# interface_circuit.net
KiCad netlist of a schematic drawn in EAGLE
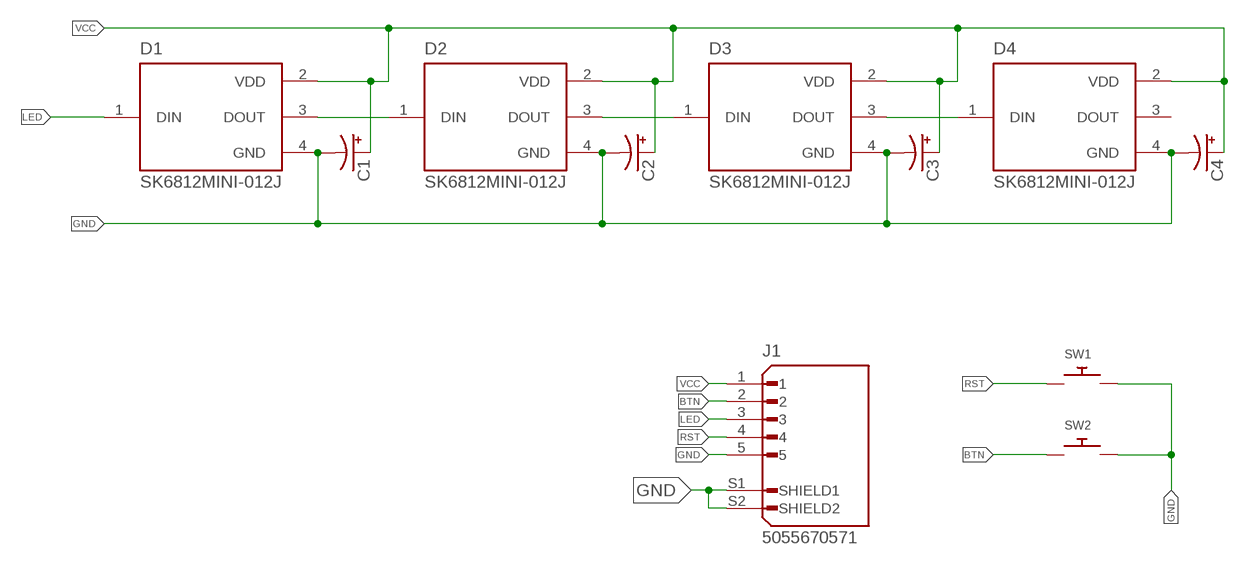
[diagram p0: schematic, sheet 1]

(export (version "E")
  (design (tool "Eeschema 10.0.6"))
  (components
    (comp (ref "C1")
      (value "CAP_POL1206")
      (footprint "eagle-import:EIA3216")
      (libsource (lib "eagle-import") (part "CAP_POL1206"))
    )
    (comp (ref "C2")
      (value "CAP_POL1206")
      (footprint "eagle-import:EIA3216")
      (libsource (lib "eagle-import") (part "CAP_POL1206"))
    )
    (comp (ref "C3")
      (value "CAP_POL1206")
      (footprint "eagle-import:EIA3216")
      (libsource (lib "eagle-import") (part "CAP_POL1206"))
    )
    (comp (ref "C4")
      (value "CAP_POL1206")
      (footprint "eagle-import:EIA3216")
      (libsource (lib "eagle-import") (part "CAP_POL1206"))
    )
    (comp (ref "D1")
      (value "SK6812MINI-012J")
      (footprint "eagle-import:LED_SK6812MINI-012")
      (fields
        (field (name "MF") "DONGGUANG OPSCO OPTOELECTRONICS CO., LTD")
        (field (name "MP") "SK6812MINI-012")
      )
      (libsource (lib "eagle-import") (part "SK6812MINI-012J"))
    )
    (comp (ref "D2")
      (value "SK6812MINI-012J")
      (footprint "eagle-import:LED_SK6812MINI-012")
      (fields
        (field (name "MF") "DONGGUANG OPSCO OPTOELECTRONICS CO., LTD")
        (field (name "MP") "SK6812MINI-012")
      )
      (libsource (lib "eagle-import") (part "SK6812MINI-012J"))
    )
    (comp (ref "D3")
      (value "SK6812MINI-012J")
      (footprint "eagle-import:LED_SK6812MINI-012")
      (fields
        (field (name "MF") "DONGGUANG OPSCO OPTOELECTRONICS CO., LTD")
        (field (name "MP") "SK6812MINI-012")
      )
      (libsource (lib "eagle-import") (part "SK6812MINI-012J"))
    )
    (comp (ref "D4")
      (value "SK6812MINI-012J")
      (footprint "eagle-import:LED_SK6812MINI-012")
      (fields
        (field (name "MF") "DONGGUANG OPSCO OPTOELECTRONICS CO., LTD")
        (field (name "MP") "SK6812MINI-012")
      )
      (libsource (lib "eagle-import") (part "SK6812MINI-012J"))
    )
    (comp (ref "J1")
      (value "5055670571")
      (footprint "eagle-import:MOLEX_5055670571")
      (fields (field (name "MANUFACTURER") "Molex"))
      (libsource (lib "eagle-import") (part "5055670571"))
    )
    (comp (ref "SW1")
      (value "SWITCH_PUSHBUTTONSOFTTOUCHSMD_SJ")
      (footprint "eagle-import:PUSHBUTTON_SMD_SJ")
      (libsource (lib "eagle-import") (part "SWITCH_PUSHBUTTONSOFTTOUCHSMD_SJ"))
    )
    (comp (ref "SW2")
      (value "SWITCH_PUSHBUTTONSOFTTOUCHSMD_SJ")
      (footprint "eagle-import:PUSHBUTTON_SMD_SJ")
      (libsource (lib "eagle-import") (part "SWITCH_PUSHBUTTONSOFTTOUCHSMD_SJ"))
    )
  )
  (nets
    (net (code "1") (name "BTN") (class "Default")
      (node (ref "J1") (pin "2") (pinfunction "2_2") (pintype "passive"))
      (node (ref "SW2") (pin "P$1") (pinfunction "P$1_P$1") (pintype "passive"))
    )
    (net (code "2") (name "GND") (class "Default")
      (node (ref "C1") (pin "C") (pinfunction "-_C") (pintype "passive"))
      (node (ref "C2") (pin "C") (pinfunction "-_C") (pintype "passive"))
      (node (ref "C3") (pin "C") (pinfunction "-_C") (pintype "passive"))
      (node (ref "C4") (pin "C") (pinfunction "-_C") (pintype "passive"))
      (node (ref "D1") (pin "4") (pinfunction "GND_4") (pintype "power_in"))
      (node (ref "D2") (pin "4") (pinfunction "GND_4") (pintype "power_in"))
      (node (ref "D3") (pin "4") (pinfunction "GND_4") (pintype "power_in"))
      (node (ref "D4") (pin "4") (pinfunction "GND_4") (pintype "power_in"))
      (node (ref "J1") (pin "5") (pinfunction "5_5") (pintype "passive"))
      (node (ref "J1") (pin "S1") (pinfunction "SHIELD1_S1") (pintype "passive"))
      (node (ref "J1") (pin "S2") (pinfunction "SHIELD2_S2") (pintype "passive"))
      (node (ref "SW1") (pin "P$2") (pinfunction "P$2_P$2") (pintype "passive"))
      (node (ref "SW2") (pin "P$2") (pinfunction "P$2_P$2") (pintype "passive"))
    )
    (net (code "3") (name "LED") (class "Default")
      (node (ref "D1") (pin "1") (pinfunction "DIN_1") (pintype "input"))
      (node (ref "J1") (pin "3") (pinfunction "3_3") (pintype "passive"))
    )
    (net (code "4") (name "Net-(D1-DOUT)") (class "Default")
      (node (ref "D1") (pin "3") (pinfunction "DOUT_3") (pintype "output"))
      (node (ref "D2") (pin "1") (pinfunction "DIN_1") (pintype "input"))
    )
    (net (code "5") (name "Net-(D2-DOUT)") (class "Default")
      (node (ref "D2") (pin "3") (pinfunction "DOUT_3") (pintype "output"))
      (node (ref "D3") (pin "1") (pinfunction "DIN_1") (pintype "input"))
    )
    (net (code "6") (name "Net-(D3-DOUT)") (class "Default")
      (node (ref "D3") (pin "3") (pinfunction "DOUT_3") (pintype "output"))
      (node (ref "D4") (pin "1") (pinfunction "DIN_1") (pintype "input"))
    )
    (net (code "7") (name "RST") (class "Default")
      (node (ref "J1") (pin "4") (pinfunction "4_4") (pintype "passive"))
      (node (ref "SW1") (pin "P$1") (pinfunction "P$1_P$1") (pintype "passive"))
    )
    (net (code "8") (name "VCC") (class "Default")
      (node (ref "C1") (pin "A") (pinfunction "+_A") (pintype "passive"))
      (node (ref "C2") (pin "A") (pinfunction "+_A") (pintype "passive"))
      (node (ref "C3") (pin "A") (pinfunction "+_A") (pintype "passive"))
      (node (ref "C4") (pin "A") (pinfunction "+_A") (pintype "passive"))
      (node (ref "D1") (pin "2") (pinfunction "VDD_2") (pintype "power_in"))
      (node (ref "D2") (pin "2") (pinfunction "VDD_2") (pintype "power_in"))
      (node (ref "D3") (pin "2") (pinfunction "VDD_2") (pintype "power_in"))
      (node (ref "D4") (pin "2") (pinfunction "VDD_2") (pintype "power_in"))
      (node (ref "J1") (pin "1") (pinfunction "1_1") (pintype "passive"))
    )
    (net (code "9") (name "unconnected-(D4-DOUT-Pad3)") (class "Default")
      (node (ref "D4") (pin "3") (pinfunction "DOUT_3") (pintype "output"))
    )
  )
)
